# design.net
KiCad netlist of a schematic drawn in Altium Designer
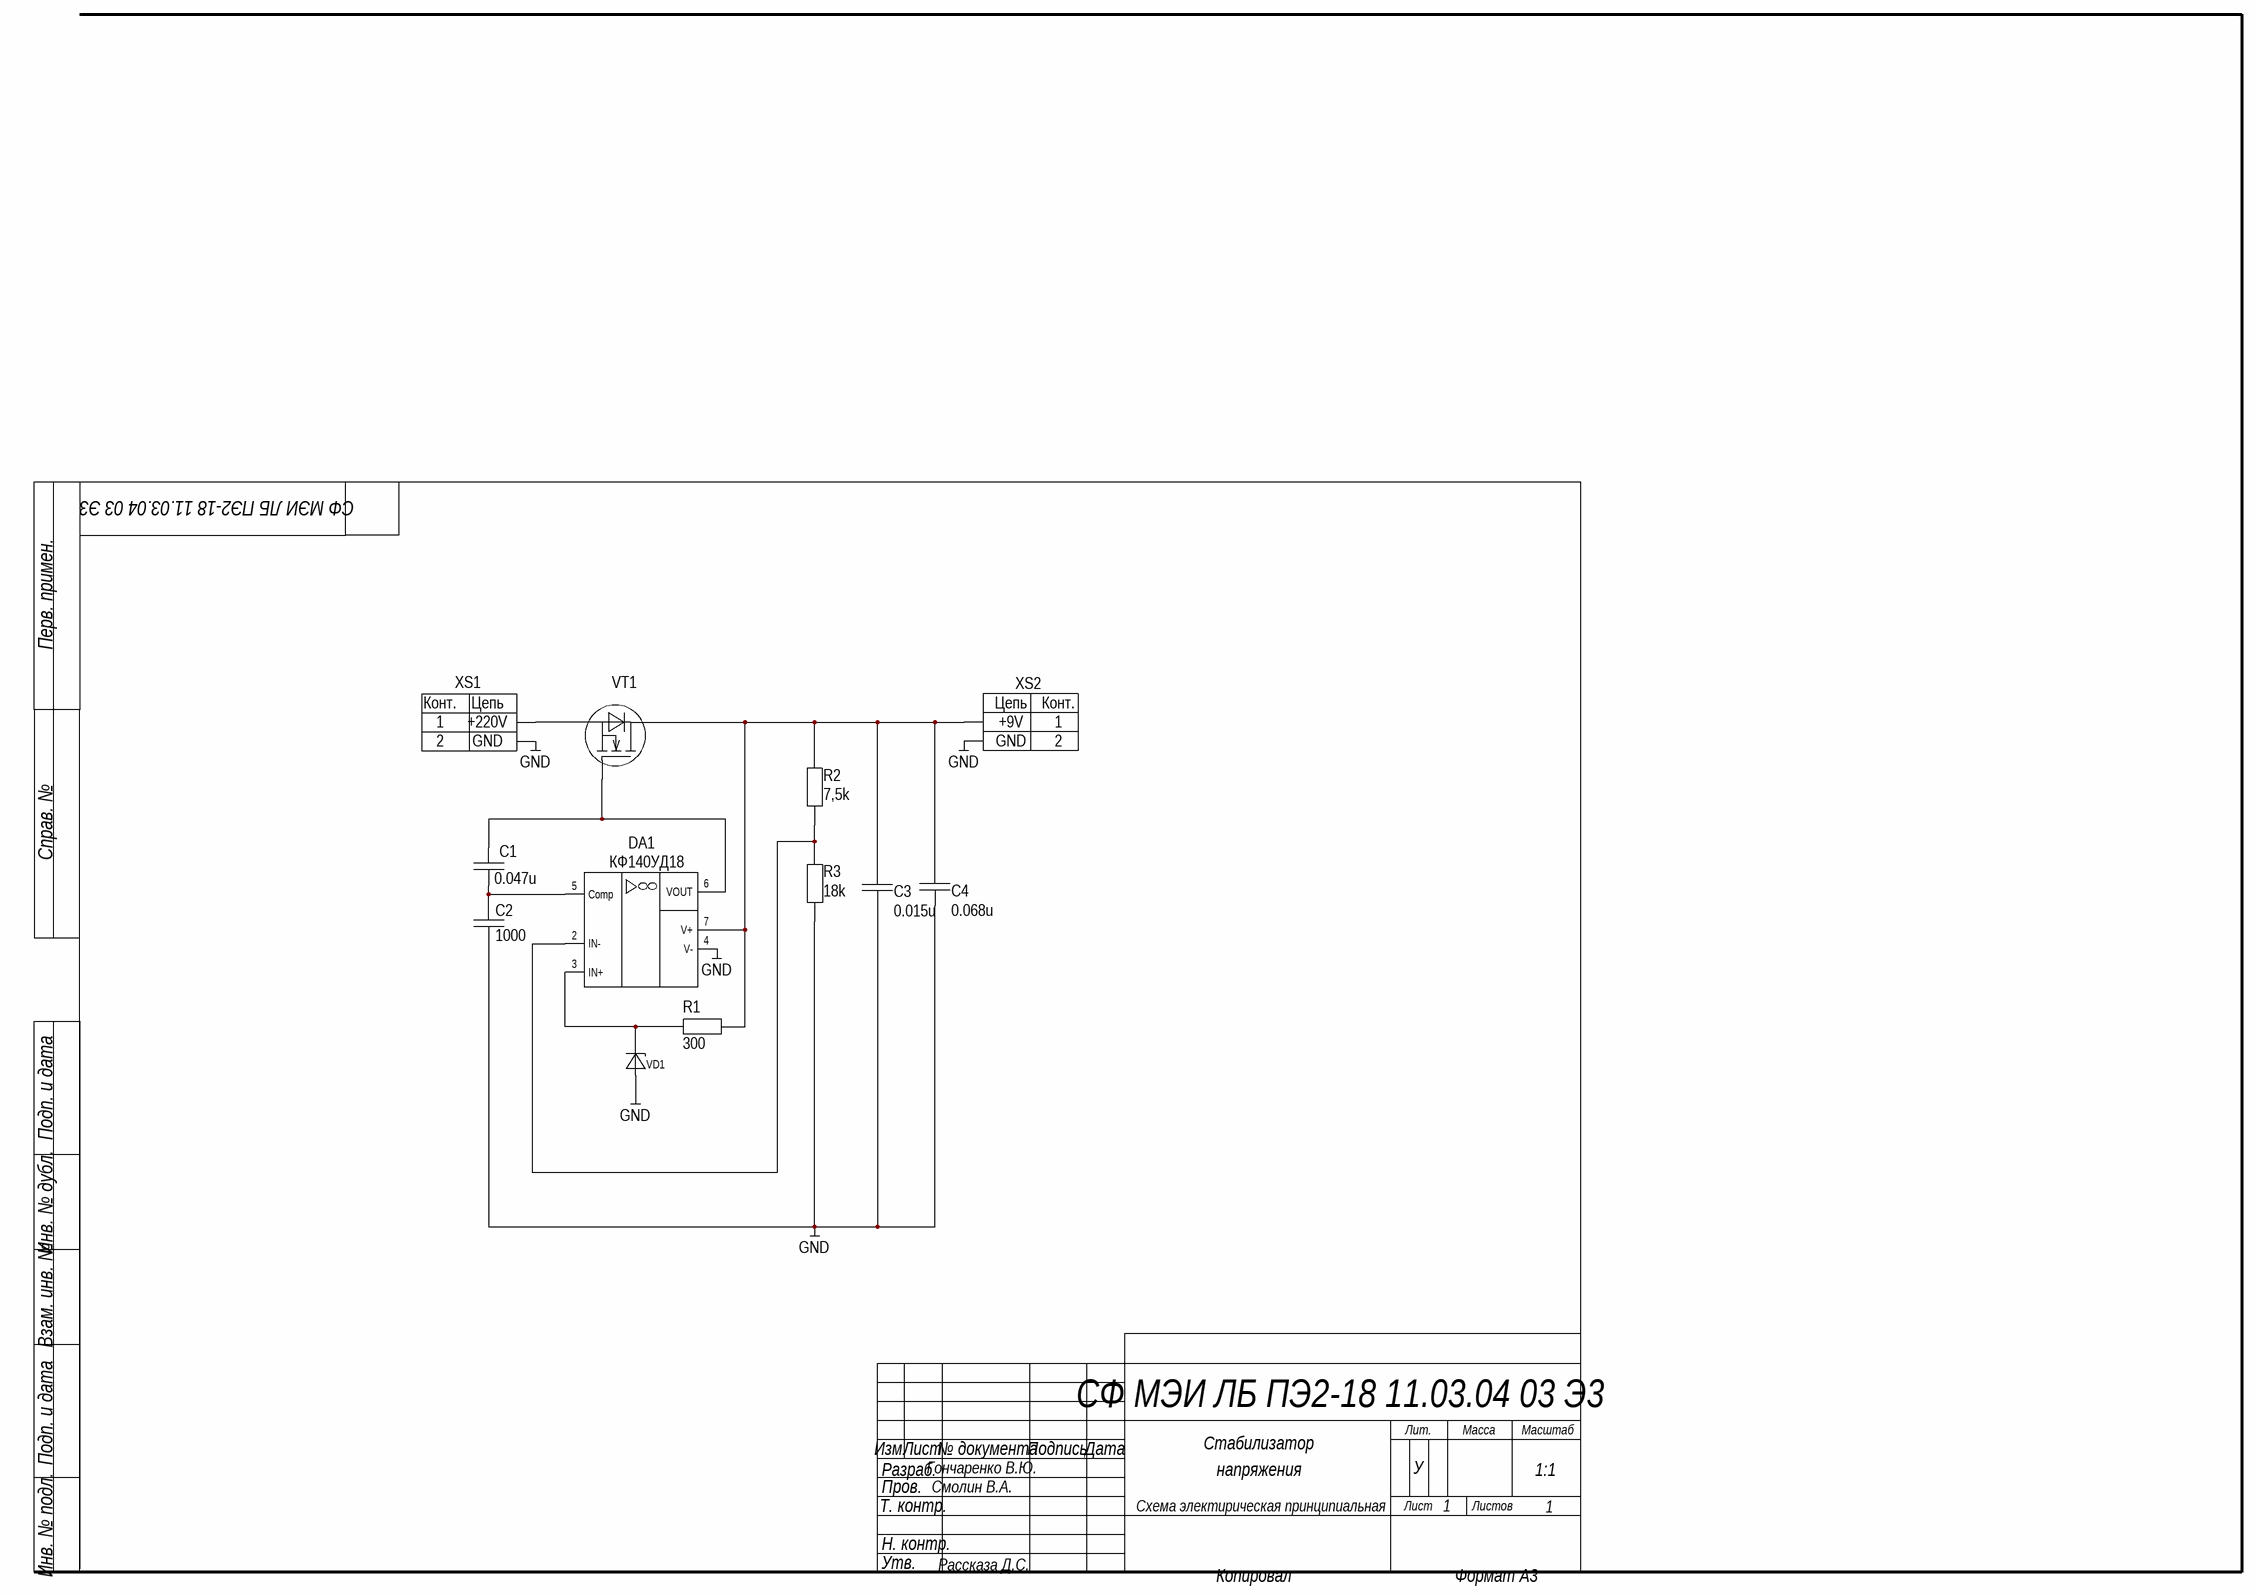
[diagram p0: Схема принципиальная.SchDoc]

(export (version "E")
  (design (tool "Eeschema 10.0.6"))
  (components
    (comp (ref "C1")
      (value "0.047u")
      (footprint "0805")
      (description "К53-68\"R\"-25В-0.047 мкФ ±10%")
      (libsource (lib "УГО") (part "К53-68{dblquote}R{dblquote}-25В-0.047 мкФ ±10% 0805_3"))
    )
    (comp (ref "C2")
      (value "1000")
      (footprint "0805")
      (description "К53-68\"R\"-25В-1000 пФ ±10%")
      (libsource (lib "УГО") (part "К53-68{dblquote}R{dblquote}-25В-1000 пФ ±10% 0805_2"))
    )
    (comp (ref "C3")
      (value "0.015u")
      (footprint "0805")
      (description "К53-68\"R\"-25В-0.015 мкФ ±10%")
      (libsource (lib "УГО") (part "К53-68{dblquote}R{dblquote}-25В-0.015 мкФ ±10% 0805_1"))
    )
    (comp (ref "C4")
      (value "0.068u")
      (footprint "0805")
      (description "К53-68\"R\"-25В-0.068 мкФ ±10%")
      (libsource (lib "УГО") (part "К53-68{dblquote}R{dblquote}-25В-0.068 мкФ ±10% 0805"))
    )
    (comp (ref "DA1") (value "КФ140УД18") (footprint "SOIC-8") (libsource (lib "УГО") (part "КФ140УД18")))
    (comp (ref "R1")
      (value "300")
      (footprint "0805")
      (description "0805-0.125 Вт -300 Ом±5%")
      (libsource (lib "УГО") (part "0.125Вт 0805 300 Ом, 5%, Чип резистор (SMD)"))
    )
    (comp (ref "R2")
      (value "7,5k")
      (footprint "0805")
      (description "0805-0.125 Вт -7,5 кОм±5%")
      (libsource (lib "УГО") (part "0.125Вт 0805 7,5 кОм, 5%, Чип резистор (SMD)"))
    )
    (comp (ref "R3")
      (value "18k")
      (footprint "0805")
      (description "0805-0.125 Вт -18 кОм±5%")
      (libsource (lib "УГО") (part "0.125Вт 0805 18 кОм, 5%, Чип резистор (SMD)"))
    )
    (comp (ref "VD1") (value "MMSZ5235B") (footprint "SOD-123") (libsource (lib "УГО") (part "MMSZ5235B")))
    (comp (ref "VT1")
      (value "IRLML2402TRPBF")
      (footprint "SOT23")
      (description "SI2304DDS-T1-GE3")
      (libsource (lib "УГО") (part "IRLML2402TRPBF"))
    )
    (comp (ref "XS1")
      (value "XS 2 pin 220 B")
      (footprint "DG126-5.0-02P")
      (libsource (lib "УГО") (part "XS 2 pin 220 B"))
    )
    (comp (ref "XS2")
      (value "XS 2 pin 9v")
      (footprint "DG126-5.0-02P")
      (libsource (lib "УГО") (part "XS 2 pin 9v"))
    )
  )
  (nets
    (net (code "1") (name "GND") (class "Default")
      (node (ref "C2") (pin "1") (pinfunction "1_1") (pintype "passive"))
      (node (ref "C3") (pin "2") (pinfunction "2_2") (pintype "passive"))
      (node (ref "C4") (pin "1") (pinfunction "1_1") (pintype "passive"))
      (node (ref "DA1") (pin "4") (pinfunction "V-_4") (pintype "passive"))
      (node (ref "R3") (pin "1") (pinfunction "1_1") (pintype "passive"))
      (node (ref "VD1") (pin "1") (pinfunction "In_1") (pintype "passive"))
      (node (ref "XS1") (pin "2") (pinfunction "Pin2_2") (pintype "passive"))
      (node (ref "XS2") (pin "2") (pinfunction "Pin2_2") (pintype "passive"))
    )
    (net (code "2") (name "Net-(DA1-Comp)") (class "Default")
      (node (ref "C1") (pin "1") (pinfunction "1_1") (pintype "passive"))
      (node (ref "C2") (pin "2") (pinfunction "2_2") (pintype "passive"))
      (node (ref "DA1") (pin "5") (pinfunction "Comp_5") (pintype "passive"))
    )
    (net (code "3") (name "Net-(DA1-IN+)") (class "Default")
      (node (ref "DA1") (pin "3") (pinfunction "IN+_3") (pintype "passive"))
      (node (ref "R1") (pin "1") (pinfunction "1_1") (pintype "passive"))
      (node (ref "VD1") (pin "2") (pinfunction "Out_2") (pintype "passive"))
    )
    (net (code "4") (name "Net-(DA1-IN-)") (class "Default")
      (node (ref "DA1") (pin "2") (pinfunction "IN-_2") (pintype "passive"))
      (node (ref "R2") (pin "1") (pinfunction "1_1") (pintype "passive"))
      (node (ref "R3") (pin "2") (pinfunction "2_2") (pintype "passive"))
    )
    (net (code "5") (name "Net-(DA1-V+)") (class "Default")
      (node (ref "C3") (pin "1") (pinfunction "1_1") (pintype "passive"))
      (node (ref "C4") (pin "2") (pinfunction "2_2") (pintype "passive"))
      (node (ref "DA1") (pin "7") (pinfunction "V+_7") (pintype "passive"))
      (node (ref "R1") (pin "2") (pinfunction "2_2") (pintype "passive"))
      (node (ref "R2") (pin "2") (pinfunction "2_2") (pintype "passive"))
      (node (ref "VT1") (pin "3") (pinfunction "D_3") (pintype "passive"))
      (node (ref "XS2") (pin "1") (pinfunction "Pin1_1") (pintype "passive"))
    )
    (net (code "6") (name "Net-(DA1-VOUT)") (class "Default")
      (node (ref "C1") (pin "2") (pinfunction "2_2") (pintype "passive"))
      (node (ref "DA1") (pin "6") (pinfunction "VOUT_6") (pintype "passive"))
      (node (ref "VT1") (pin "1") (pinfunction "G_1") (pintype "passive"))
    )
    (net (code "7") (name "Net-(VT1-S)") (class "Default")
      (node (ref "VT1") (pin "2") (pinfunction "S_2") (pintype "passive"))
      (node (ref "XS1") (pin "1") (pinfunction "Pin1_1") (pintype "passive"))
    )
  )
)
